# sr_controller_v0.net
KiCad netlist of a schematic drawn in EAGLE
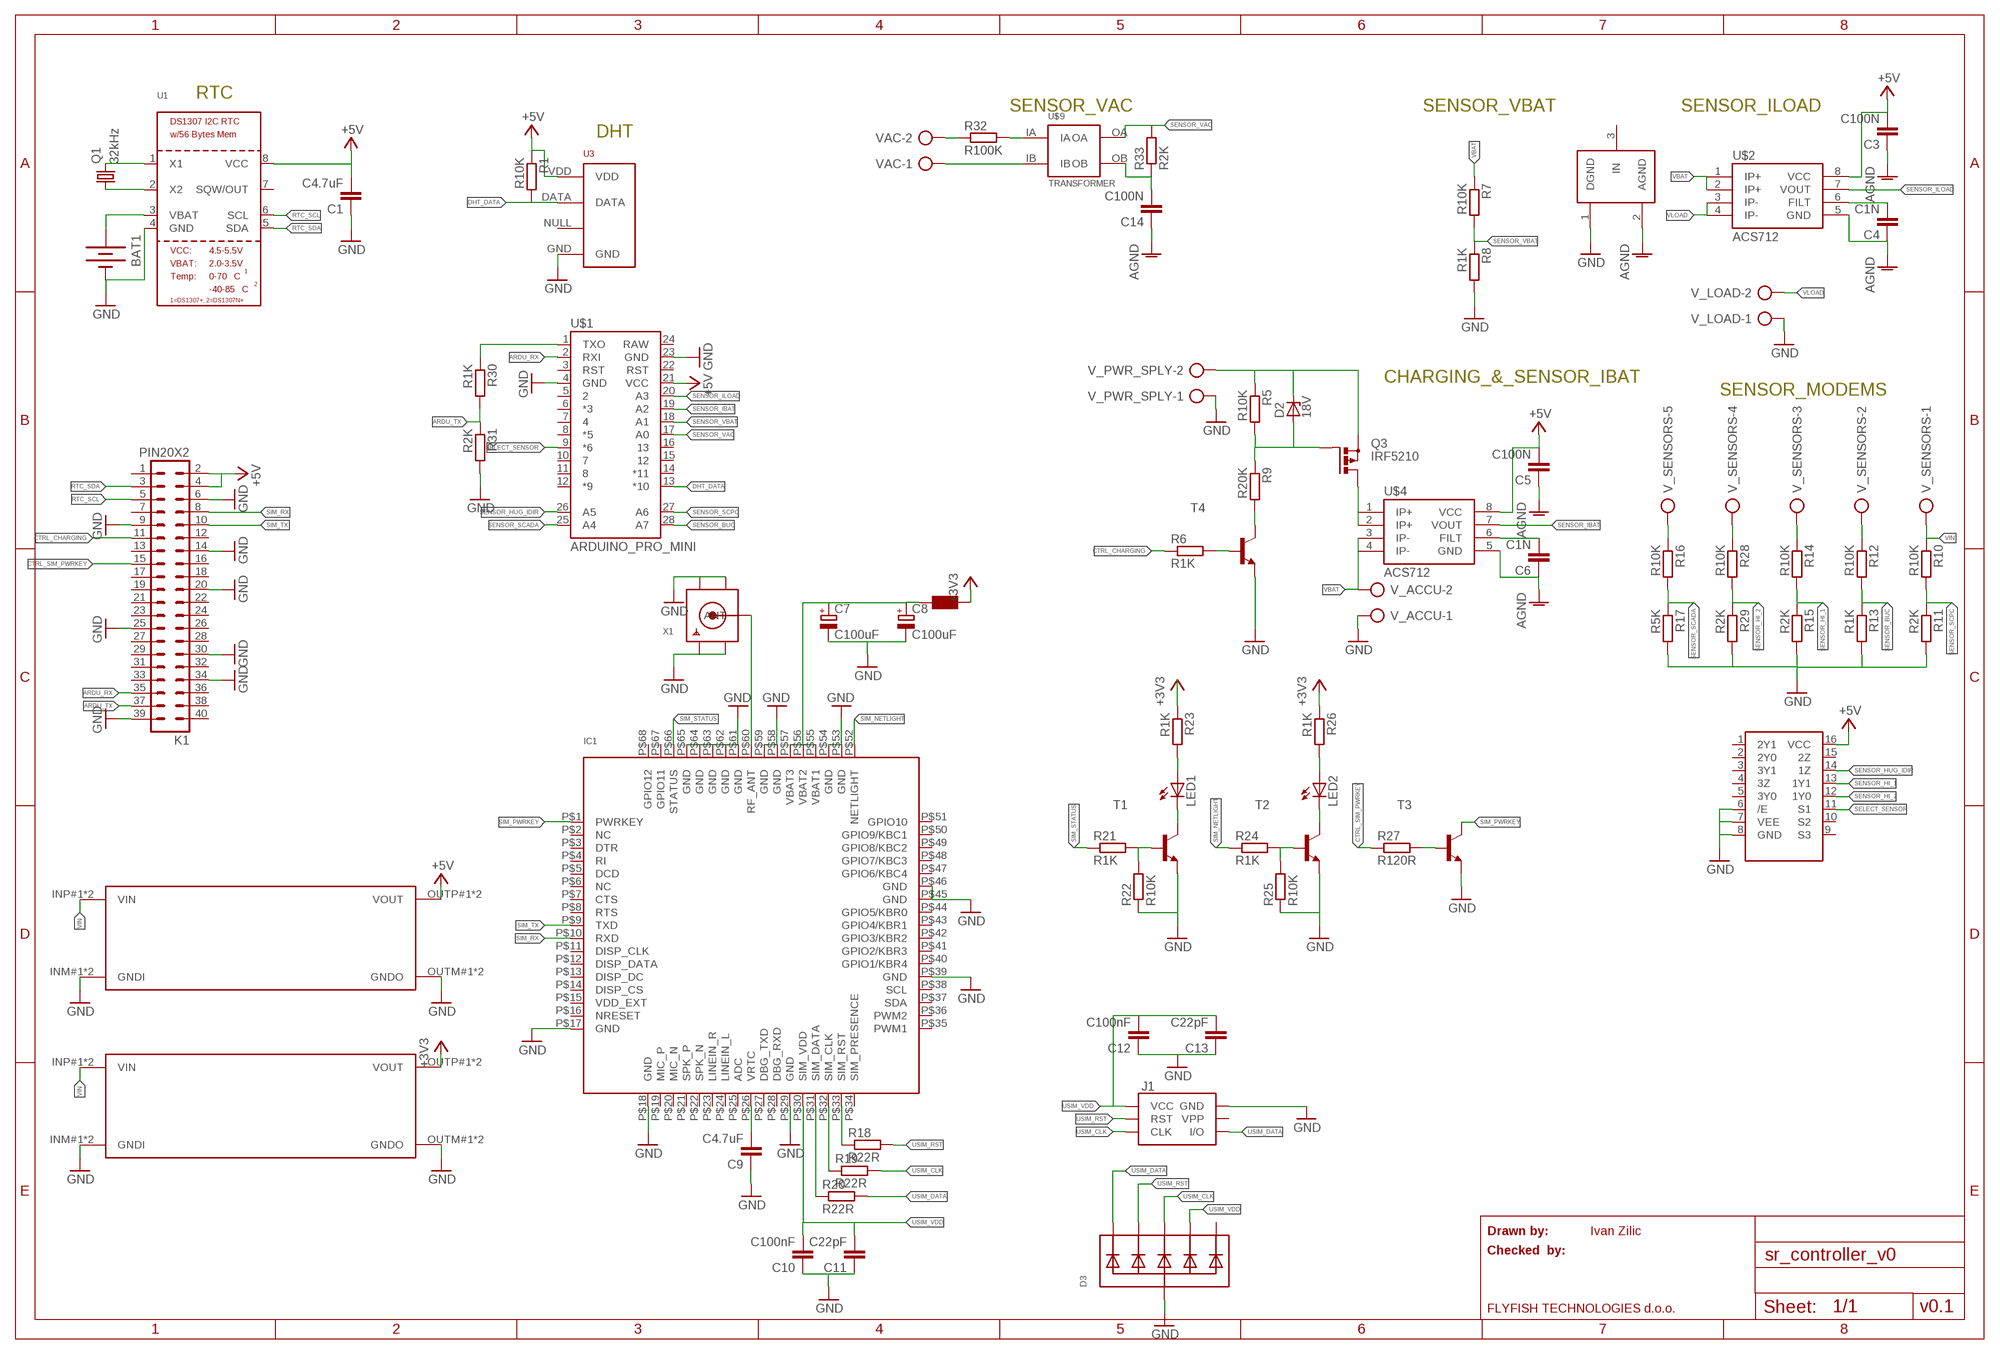
[diagram p0: schematic, sheet 1]

(export (version "E")
  (design (tool "Eeschema 10.0.6"))
  (components
    (comp (ref "BAT1")
      (value "BATTERY20PTH")
      (footprint "eagle-import:BATTCOM_20MM_PTH")
      (libsource (lib "eagle-import") (part "BATTERY20PTH"))
    )
    (comp (ref "C1")
      (value "C4.7uF")
      (footprint "eagle-import:C0805")
      (libsource (lib "eagle-import") (part "C-EUC0805"))
    )
    (comp (ref "C3")
      (value "C100N")
      (footprint "eagle-import:C0805K")
      (libsource (lib "eagle-import") (part "C-EUC0805K"))
    )
    (comp (ref "C4")
      (value "C1N")
      (footprint "eagle-import:C0805K")
      (libsource (lib "eagle-import") (part "C-EUC0805K"))
    )
    (comp (ref "C5")
      (value "C100N")
      (footprint "eagle-import:C0805K")
      (libsource (lib "eagle-import") (part "C-EUC0805K"))
    )
    (comp (ref "C6")
      (value "C1N")
      (footprint "eagle-import:C0805K")
      (libsource (lib "eagle-import") (part "C-EUC0805K"))
    )
    (comp (ref "C7")
      (value "C100uF")
      (footprint "eagle-import:153CLV-0605")
      (libsource (lib "eagle-import") (part "CPOL-EU153CLV-0605"))
    )
    (comp (ref "C8")
      (value "C100uF")
      (footprint "eagle-import:153CLV-0605")
      (libsource (lib "eagle-import") (part "CPOL-EU153CLV-0605"))
    )
    (comp (ref "C9")
      (value "C4.7uF")
      (footprint "eagle-import:C0805")
      (libsource (lib "eagle-import") (part "C-EUC0805"))
    )
    (comp (ref "C10")
      (value "C100nF")
      (footprint "eagle-import:C0805")
      (libsource (lib "eagle-import") (part "C-EUC0805"))
    )
    (comp (ref "C11")
      (value "C22pF")
      (footprint "eagle-import:C0805")
      (libsource (lib "eagle-import") (part "C-EUC0805"))
    )
    (comp (ref "C12")
      (value "C100nF")
      (footprint "eagle-import:C0805")
      (libsource (lib "eagle-import") (part "C-EUC0805"))
    )
    (comp (ref "C13")
      (value "C22pF")
      (footprint "eagle-import:C0805")
      (libsource (lib "eagle-import") (part "C-EUC0805"))
    )
    (comp (ref "C14")
      (value "C100N")
      (footprint "eagle-import:C0805K")
      (libsource (lib "eagle-import") (part "C-EUC0805K"))
    )
    (comp (ref "D2")
      (value "18V")
      (footprint "eagle-import:DO41Z10")
      (libsource (lib "eagle-import") (part "ZENER-DIODEDO41Z10"))
    )
    (comp (ref "D3")
      (value "TVSARRAY_5LANE")
      (footprint "eagle-import:SOT363")
      (libsource (lib "eagle-import") (part "TVSARRAY_5LANE"))
    )
    (comp (ref "IC1")
      (value "GSM_SIM900_LITERAL")
      (footprint "eagle-import:SIM900_SMT")
      (libsource (lib "eagle-import") (part "GSM_SIM900_LITERAL"))
    )
    (comp (ref "J1")
      (value "SIMHOLDERSIM")
      (footprint "eagle-import:SIMHOLDER")
      (libsource (lib "eagle-import") (part "SIMHOLDERSIM"))
    )
    (comp (ref "K1")
      (value "PIN20X2")
      (footprint "eagle-import:PIN_20X2")
      (libsource (lib "eagle-import") (part "PIN20X2"))
    )
    (comp (ref "LED1")
      (value "LEDCHIPLED_0805")
      (footprint "eagle-import:CHIPLED_0805")
      (libsource (lib "eagle-import") (part "LEDCHIPLED_0805"))
    )
    (comp (ref "LED2")
      (value "LEDCHIPLED_0805")
      (footprint "eagle-import:CHIPLED_0805")
      (libsource (lib "eagle-import") (part "LEDCHIPLED_0805"))
    )
    (comp (ref "Q1")
      (value "32kHz")
      (footprint "eagle-import:TC38H")
      (libsource (lib "eagle-import") (part "CRYSTALTC38H"))
    )
    (comp (ref "Q3")
      (value "IRF5210")
      (footprint "eagle-import:TO220BV")
      (libsource (lib "eagle-import") (part "PMOSFET_PTO220BV"))
    )
    (comp (ref "R1")
      (value "R10K")
      (footprint "eagle-import:R0805")
      (libsource (lib "eagle-import") (part "R-EU_R0805"))
    )
    (comp (ref "R5")
      (value "R10K")
      (footprint "eagle-import:R0805")
      (libsource (lib "eagle-import") (part "R-EU_R0805"))
    )
    (comp (ref "R6")
      (value "R1K")
      (footprint "eagle-import:R0805")
      (libsource (lib "eagle-import") (part "R-EU_R0805"))
    )
    (comp (ref "R7")
      (value "R10K")
      (footprint "eagle-import:R0805")
      (libsource (lib "eagle-import") (part "R-EU_R0805"))
    )
    (comp (ref "R8")
      (value "R1K")
      (footprint "eagle-import:R0805")
      (libsource (lib "eagle-import") (part "R-EU_R0805"))
    )
    (comp (ref "R9")
      (value "R20K")
      (footprint "eagle-import:R0805")
      (libsource (lib "eagle-import") (part "R-EU_R0805"))
    )
    (comp (ref "R10")
      (value "R10K")
      (footprint "eagle-import:R0805")
      (libsource (lib "eagle-import") (part "R-EU_R0805"))
    )
    (comp (ref "R11")
      (value "R2K")
      (footprint "eagle-import:R0805")
      (libsource (lib "eagle-import") (part "R-EU_R0805"))
    )
    (comp (ref "R12")
      (value "R10K")
      (footprint "eagle-import:R0805")
      (libsource (lib "eagle-import") (part "R-EU_R0805"))
    )
    (comp (ref "R13")
      (value "R1K")
      (footprint "eagle-import:R0805")
      (libsource (lib "eagle-import") (part "R-EU_R0805"))
    )
    (comp (ref "R14")
      (value "R10K")
      (footprint "eagle-import:R0805")
      (libsource (lib "eagle-import") (part "R-EU_R0805"))
    )
    (comp (ref "R15")
      (value "R2K")
      (footprint "eagle-import:R0805")
      (libsource (lib "eagle-import") (part "R-EU_R0805"))
    )
    (comp (ref "R16")
      (value "R10K")
      (footprint "eagle-import:R0805")
      (libsource (lib "eagle-import") (part "R-EU_R0805"))
    )
    (comp (ref "R17")
      (value "R5K")
      (footprint "eagle-import:R0805")
      (libsource (lib "eagle-import") (part "R-EU_R0805"))
    )
    (comp (ref "R18")
      (value "R22R")
      (footprint "eagle-import:R0805")
      (libsource (lib "eagle-import") (part "R-EU_R0805"))
    )
    (comp (ref "R19")
      (value "R22R")
      (footprint "eagle-import:R0805")
      (libsource (lib "eagle-import") (part "R-EU_R0805"))
    )
    (comp (ref "R20")
      (value "R22R")
      (footprint "eagle-import:R0805")
      (libsource (lib "eagle-import") (part "R-EU_R0805"))
    )
    (comp (ref "R21")
      (value "R1K")
      (footprint "eagle-import:R0805")
      (libsource (lib "eagle-import") (part "R-EU_R0805"))
    )
    (comp (ref "R22")
      (value "R10K")
      (footprint "eagle-import:R0805")
      (libsource (lib "eagle-import") (part "R-EU_R0805"))
    )
    (comp (ref "R23")
      (value "R1K")
      (footprint "eagle-import:R0805")
      (libsource (lib "eagle-import") (part "R-EU_R0805"))
    )
    (comp (ref "R24")
      (value "R1K")
      (footprint "eagle-import:R0805")
      (libsource (lib "eagle-import") (part "R-EU_R0805"))
    )
    (comp (ref "R25")
      (value "R10K")
      (footprint "eagle-import:R0805")
      (libsource (lib "eagle-import") (part "R-EU_R0805"))
    )
    (comp (ref "R26")
      (value "R1K")
      (footprint "eagle-import:R0805")
      (libsource (lib "eagle-import") (part "R-EU_R0805"))
    )
    (comp (ref "R27")
      (value "R120R")
      (footprint "eagle-import:R0805")
      (libsource (lib "eagle-import") (part "R-EU_R0805"))
    )
    (comp (ref "R28")
      (value "R10K")
      (footprint "eagle-import:R0805")
      (libsource (lib "eagle-import") (part "R-EU_R0805"))
    )
    (comp (ref "R29")
      (value "R2K")
      (footprint "eagle-import:R0805")
      (libsource (lib "eagle-import") (part "R-EU_R0805"))
    )
    (comp (ref "R30")
      (value "R1K")
      (footprint "eagle-import:R0805")
      (libsource (lib "eagle-import") (part "R-EU_R0805"))
    )
    (comp (ref "R31")
      (value "R2K")
      (footprint "eagle-import:R0805")
      (libsource (lib "eagle-import") (part "R-EU_R0805"))
    )
    (comp (ref "R32")
      (value "R100K")
      (footprint "eagle-import:0309V")
      (libsource (lib "eagle-import") (part "R-EU_0309/V"))
    )
    (comp (ref "R33")
      (value "R2K")
      (footprint "eagle-import:0309V")
      (libsource (lib "eagle-import") (part "R-EU_0309/V"))
    )
    (comp (ref "T1")
      (value "MMBT2222ALT1-NPN-SOT23-BEC")
      (footprint "eagle-import:SOT23-BEC")
      (libsource (lib "eagle-import") (part "-NPN-SOT23-BECMMBT2222ALT1"))
    )
    (comp (ref "T2")
      (value "MMBT2222ALT1-NPN-SOT23-BEC")
      (footprint "eagle-import:SOT23-BEC")
      (libsource (lib "eagle-import") (part "-NPN-SOT23-BECMMBT2222ALT1"))
    )
    (comp (ref "T3")
      (value "MMBT2222ALT1-NPN-SOT23-BEC")
      (footprint "eagle-import:SOT23-BEC")
      (libsource (lib "eagle-import") (part "-NPN-SOT23-BECMMBT2222ALT1"))
    )
    (comp (ref "T4")
      (value "MMBT2222ALT1-NPN-SOT23-BEC")
      (footprint "eagle-import:SOT23-BEC")
      (libsource (lib "eagle-import") (part "-NPN-SOT23-BECMMBT2222ALT1"))
    )
    (comp (ref "U$1")
      (value "ARDUINO_PRO_MINI")
      (footprint "eagle-import:ARDUINO_PRO_MINI")
      (libsource (lib "eagle-import") (part "ARDUINO_PRO_MINI"))
    )
    (comp (ref "U$2")
      (value "ACS712")
      (footprint "eagle-import:SO08")
      (libsource (lib "eagle-import") (part "ACS712"))
    )
    (comp (ref "U$3")
      (value "GND_CONNECT")
      (footprint "eagle-import:GND_CONNECT")
      (libsource (lib "eagle-import") (part "GND_CONNECT"))
    )
    (comp (ref "U$4")
      (value "ACS712")
      (footprint "eagle-import:SO08")
      (libsource (lib "eagle-import") (part "ACS712"))
    )
    (comp (ref "U$5")
      (value "FB0603")
      (footprint "eagle-import:L0603")
      (libsource (lib "eagle-import") (part "L0603"))
    )
    (comp (ref "U$6")
      (value "DCDCMODULE_SMALL")
      (footprint "eagle-import:DCDCMODULE-SMALL")
      (libsource (lib "eagle-import") (part "DCDCMODULE_SMALL"))
    )
    (comp (ref "U$7")
      (value "DCDCMODULE_SMALL")
      (footprint "eagle-import:DCDCMODULE-SMALL")
      (libsource (lib "eagle-import") (part "DCDCMODULE_SMALL"))
    )
    (comp (ref "U$8")
      (value "74HC4053D")
      (footprint "eagle-import:SO16")
      (libsource (lib "eagle-import") (part "74HC4053D"))
    )
    (comp (ref "U$9")
      (value "TRANSFORMER")
      (footprint "eagle-import:TV16")
      (libsource (lib "eagle-import") (part "TRANSFORMER"))
    )
    (comp (ref "U1")
      (value "RTC_DS1307")
      (footprint "eagle-import:SOIC8_150MIL")
      (libsource (lib "eagle-import") (part "RTC_DS1307"))
    )
    (comp (ref "U3")
      (value "RHT03_DHT-22_AM2302")
      (footprint "eagle-import:RHT03_DHT-22")
      (libsource (lib "eagle-import") (part "RHT03_DHT-22_AM2302"))
    )
    (comp (ref "VAC")
      (value "AK300/2")
      (footprint "eagle-import:AK300_2")
      (libsource (lib "eagle-import") (part "AK300/2"))
    )
    (comp (ref "V_ACCU")
      (value "AK300/2")
      (footprint "eagle-import:AK300_2")
      (libsource (lib "eagle-import") (part "AK300/2"))
    )
    (comp (ref "V_LOAD")
      (value "AK300/2")
      (footprint "eagle-import:AK300_2")
      (libsource (lib "eagle-import") (part "AK300/2"))
    )
    (comp (ref "V_PWR_SPLY")
      (value "AK300/2")
      (footprint "eagle-import:AK300_2")
      (libsource (lib "eagle-import") (part "AK300/2"))
    )
    (comp (ref "V_SENSORS")
      (value "AK300/5")
      (footprint "eagle-import:AK300_5")
      (libsource (lib "eagle-import") (part "AK300/5"))
    )
    (comp (ref "X1")
      (value "SMACONNECTOR")
      (footprint "eagle-import:SMA90_DIP")
      (libsource (lib "eagle-import") (part "SMACONNECTOR"))
    )
  )
  (nets
    (net (code "1") (name "+3V3") (class "Default")
      (node (ref "R23") (pin "1") (pinfunction "1_1") (pintype "passive"))
      (node (ref "R26") (pin "1") (pinfunction "1_1") (pintype "passive"))
      (node (ref "U$5") (pin "2") (pinfunction "P$2_2") (pintype "bidirectional"))
      (node (ref "U$7") (pin "OUTP#1") (pinfunction "VOUT_OUTP#1") (pintype "bidirectional"))
      (node (ref "U$7") (pin "OUTP#2") (pinfunction "VOUT_OUTP#2") (pintype "bidirectional"))
    )
    (net (code "2") (name "+5V") (class "Default")
      (node (ref "C1") (pin "2") (pinfunction "2_2") (pintype "passive"))
      (node (ref "C3") (pin "2") (pinfunction "2_2") (pintype "passive"))
      (node (ref "C5") (pin "2") (pinfunction "2_2") (pintype "passive"))
      (node (ref "K1") (pin "2") (pinfunction "2_2") (pintype "passive"))
      (node (ref "K1") (pin "4") (pinfunction "4_4") (pintype "passive"))
      (node (ref "R1") (pin "1") (pinfunction "1_1") (pintype "passive"))
      (node (ref "U$1") (pin "21") (pinfunction "VCC_21") (pintype "bidirectional"))
      (node (ref "U$2") (pin "8") (pinfunction "VCC_8") (pintype "bidirectional"))
      (node (ref "U$4") (pin "8") (pinfunction "VCC_8") (pintype "bidirectional"))
      (node (ref "U$6") (pin "OUTP#1") (pinfunction "VOUT_OUTP#1") (pintype "bidirectional"))
      (node (ref "U$6") (pin "OUTP#2") (pinfunction "VOUT_OUTP#2") (pintype "bidirectional"))
      (node (ref "U$8") (pin "16") (pinfunction "VCC_16") (pintype "bidirectional"))
      (node (ref "U1") (pin "8") (pinfunction "VCC_8") (pintype "bidirectional"))
      (node (ref "U3") (pin "VDD") (pinfunction "VDD_VDD") (pintype "power_in"))
    )
    (net (code "3") (name "/GPIO11") (class "Default")
      (node (ref "IC1") (pin "P$67") (pinfunction "GPIO11_P$67") (pintype "power_in"))
    )
    (net (code "4") (name "/GPIO12") (class "Default")
      (node (ref "IC1") (pin "P$68") (pinfunction "GPIO12_P$68") (pintype "power_in"))
    )
    (net (code "5") (name "AGND") (class "Default")
      (node (ref "C14") (pin "1") (pinfunction "1_1") (pintype "passive"))
      (node (ref "C3") (pin "1") (pinfunction "1_1") (pintype "passive"))
      (node (ref "C4") (pin "1") (pinfunction "1_1") (pintype "passive"))
      (node (ref "C5") (pin "1") (pinfunction "1_1") (pintype "passive"))
      (node (ref "C6") (pin "1") (pinfunction "1_1") (pintype "passive"))
      (node (ref "U$2") (pin "5") (pinfunction "GND_5") (pintype "bidirectional"))
      (node (ref "U$3") (pin "2") (pinfunction "AGND_2") (pintype "bidirectional"))
      (node (ref "U$4") (pin "5") (pinfunction "GND_5") (pintype "bidirectional"))
    )
    (net (code "6") (name "ARDU_RX") (class "Default")
      (node (ref "K1") (pin "35") (pinfunction "35_35") (pintype "passive"))
      (node (ref "U$1") (pin "2") (pinfunction "RXI_2") (pintype "bidirectional"))
    )
    (net (code "7") (name "ARDU_TX") (class "Default")
      (node (ref "K1") (pin "37") (pinfunction "37_37") (pintype "passive"))
      (node (ref "R30") (pin "2") (pinfunction "2_2") (pintype "passive"))
      (node (ref "R31") (pin "1") (pinfunction "1_1") (pintype "passive"))
    )
    (net (code "8") (name "CTRL_CHARGING") (class "Default")
      (node (ref "K1") (pin "11") (pinfunction "11_11") (pintype "passive"))
      (node (ref "R6") (pin "1") (pinfunction "1_1") (pintype "passive"))
    )
    (net (code "9") (name "CTRL_SIM_PWRKEY") (class "Default")
      (node (ref "K1") (pin "15") (pinfunction "15_15") (pintype "passive"))
      (node (ref "R27") (pin "1") (pinfunction "1_1") (pintype "passive"))
    )
    (net (code "10") (name "DHT_DATA") (class "Default")
      (node (ref "R1") (pin "2") (pinfunction "2_2") (pintype "passive"))
      (node (ref "U$1") (pin "13") (pinfunction "*10_13") (pintype "bidirectional"))
      (node (ref "U3") (pin "DATA") (pinfunction "DATA_DATA") (pintype "bidirectional"))
    )
    (net (code "11") (name "GND") (class "Default")
      (node (ref "BAT1") (pin "2") (pinfunction "-_2") (pintype "power_in"))
      (node (ref "C1") (pin "1") (pinfunction "1_1") (pintype "passive"))
      (node (ref "C10") (pin "1") (pinfunction "1_1") (pintype "passive"))
      (node (ref "C11") (pin "1") (pinfunction "1_1") (pintype "passive"))
      (node (ref "C12") (pin "1") (pinfunction "1_1") (pintype "passive"))
      (node (ref "C13") (pin "1") (pinfunction "1_1") (pintype "passive"))
      (node (ref "C7") (pin "-") (pinfunction "-_-") (pintype "passive"))
      (node (ref "C8") (pin "-") (pinfunction "-_-") (pintype "passive"))
      (node (ref "C9") (pin "1") (pinfunction "1_1") (pintype "passive"))
      (node (ref "D3") (pin "2") (pinfunction "A_2") (pintype "passive"))
      (node (ref "IC1") (pin "P$17") (pinfunction "GND_P$17") (pintype "power_in"))
      (node (ref "IC1") (pin "P$18") (pinfunction "GND_P$18") (pintype "power_in"))
      (node (ref "IC1") (pin "P$29") (pinfunction "GND_P$29") (pintype "power_in"))
      (node (ref "IC1") (pin "P$39") (pinfunction "GND_P$39") (pintype "power_in"))
      (node (ref "IC1") (pin "P$45") (pinfunction "GND_P$45") (pintype "power_in"))
      (node (ref "IC1") (pin "P$46") (pinfunction "GND_P$46") (pintype "power_in"))
      (node (ref "IC1") (pin "P$53") (pinfunction "GND_P$53") (pintype "power_in"))
      (node (ref "IC1") (pin "P$54") (pinfunction "GND_P$54") (pintype "power_in"))
      (node (ref "IC1") (pin "P$58") (pinfunction "GND_P$58") (pintype "power_in"))
      (node (ref "IC1") (pin "P$59") (pinfunction "GND_P$59") (pintype "power_in"))
      (node (ref "IC1") (pin "P$61") (pinfunction "GND_P$61") (pintype "power_in"))
      (node (ref "IC1") (pin "P$62") (pinfunction "GND_P$62") (pintype "power_in"))
      (node (ref "IC1") (pin "P$63") (pinfunction "GND_P$63") (pintype "power_in"))
      (node (ref "IC1") (pin "P$64") (pinfunction "GND_P$64") (pintype "power_in"))
      (node (ref "IC1") (pin "P$65") (pinfunction "GND_P$65") (pintype "power_in"))
      (node (ref "J1") (pin "C5") (pinfunction "GND_C5") (pintype "power_in"))
      (node (ref "K1") (pin "14") (pinfunction "14_14") (pintype "passive"))
      (node (ref "K1") (pin "20") (pinfunction "20_20") (pintype "passive"))
      (node (ref "K1") (pin "25") (pinfunction "25_25") (pintype "passive"))
      (node (ref "K1") (pin "30") (pinfunction "30_30") (pintype "passive"))
      (node (ref "K1") (pin "34") (pinfunction "34_34") (pintype "passive"))
      (node (ref "K1") (pin "39") (pinfunction "39_39") (pintype "passive"))
      (node (ref "K1") (pin "6") (pinfunction "6_6") (pintype "passive"))
      (node (ref "K1") (pin "9") (pinfunction "9_9") (pintype "passive"))
      (node (ref "R11") (pin "2") (pinfunction "2_2") (pintype "passive"))
      (node (ref "R13") (pin "2") (pinfunction "2_2") (pintype "passive"))
      (node (ref "R15") (pin "2") (pinfunction "2_2") (pintype "passive"))
      (node (ref "R17") (pin "2") (pinfunction "2_2") (pintype "passive"))
      (node (ref "R22") (pin "1") (pinfunction "1_1") (pintype "passive"))
      (node (ref "R25") (pin "1") (pinfunction "1_1") (pintype "passive"))
      (node (ref "R29") (pin "2") (pinfunction "2_2") (pintype "passive"))
      (node (ref "R31") (pin "2") (pinfunction "2_2") (pintype "passive"))
      (node (ref "R8") (pin "2") (pinfunction "2_2") (pintype "passive"))
      (node (ref "T1") (pin "E") (pinfunction "E_E") (pintype "passive"))
      (node (ref "T2") (pin "E") (pinfunction "E_E") (pintype "passive"))
      (node (ref "T3") (pin "E") (pinfunction "E_E") (pintype "passive"))
      (node (ref "T4") (pin "E") (pinfunction "E_E") (pintype "passive"))
      (node (ref "U$1") (pin "23") (pinfunction "GND_23") (pintype "bidirectional"))
      (node (ref "U$1") (pin "4") (pinfunction "GND_4") (pintype "bidirectional"))
      (node (ref "U$3") (pin "1") (pinfunction "DGND_1") (pintype "bidirectional"))
      (node (ref "U$6") (pin "INM#1") (pinfunction "GNDI_INM#1") (pintype "bidirectional"))
      (node (ref "U$6") (pin "INM#2") (pinfunction "GNDI_INM#2") (pintype "bidirectional"))
      (node (ref "U$6") (pin "OUTM#1") (pinfunction "GNDO_OUTM#1") (pintype "bidirectional"))
      (node (ref "U$6") (pin "OUTM#2") (pinfunction "GNDO_OUTM#2") (pintype "bidirectional"))
      (node (ref "U$7") (pin "INM#1") (pinfunction "GNDI_INM#1") (pintype "bidirectional"))
      (node (ref "U$7") (pin "INM#2") (pinfunction "GNDI_INM#2") (pintype "bidirectional"))
      (node (ref "U$7") (pin "OUTM#1") (pinfunction "GNDO_OUTM#1") (pintype "bidirectional"))
      (node (ref "U$7") (pin "OUTM#2") (pinfunction "GNDO_OUTM#2") (pintype "bidirectional"))
      (node (ref "U$8") (pin "6") (pinfunction "/E_6") (pintype "bidirectional"))
      (node (ref "U$8") (pin "7") (pinfunction "VEE_7") (pintype "bidirectional"))
      (node (ref "U$8") (pin "8") (pinfunction "GND_8") (pintype "bidirectional"))
      (node (ref "U1") (pin "4") (pinfunction "GND_4") (pintype "bidirectional"))
      (node (ref "U3") (pin "GND") (pinfunction "GND_GND") (pintype "power_in"))
      (node (ref "V_ACCU") (pin "1") (pinfunction "KL_1") (pintype "passive"))
      (node (ref "V_LOAD") (pin "1") (pinfunction "KL_1") (pintype "passive"))
      (node (ref "V_PWR_SPLY") (pin "1") (pinfunction "KL_1") (pintype "passive"))
      (node (ref "X1") (pin "GND1") (pinfunction "GND1_GND1") (pintype "power_in"))
      (node (ref "X1") (pin "GND2") (pinfunction "GND2_GND2") (pintype "power_in"))
      (node (ref "X1") (pin "GND3") (pinfunction "GND3_GND3") (pintype "power_in"))
      (node (ref "X1") (pin "GND4") (pinfunction "GND4_GND4") (pintype "power_in"))
    )
    (net (code "12") (name "Net-(BAT1-+)") (class "Default")
      (node (ref "BAT1") (pin "1") (pinfunction "+_1") (pintype "power_in"))
      (node (ref "U1") (pin "3") (pinfunction "VBAT_3") (pintype "bidirectional"))
    )
    (net (code "13") (name "Net-(C14-Pad2)") (class "Default")
      (node (ref "C14") (pin "2") (pinfunction "2_2") (pintype "passive"))
      (node (ref "R33") (pin "1") (pinfunction "1_1") (pintype "passive"))
      (node (ref "U$9") (pin "OB") (pinfunction "OB_OB") (pintype "bidirectional"))
    )
    (net (code "14") (name "Net-(D2-PadA)") (class "Default")
      (node (ref "D2") (pin "A") (pinfunction "A_A") (pintype "passive"))
      (node (ref "Q3") (pin "G") (pinfunction "G_G") (pintype "passive"))
      (node (ref "R5") (pin "2") (pinfunction "2_2") (pintype "passive"))
      (node (ref "R9") (pin "1") (pinfunction "1_1") (pintype "passive"))
    )
    (net (code "15") (name "Net-(IC1-RF_ANT)") (class "Default")
      (node (ref "IC1") (pin "P$60") (pinfunction "RF_ANT_P$60") (pintype "bidirectional"))
      (node (ref "X1") (pin "ANTENNA") (pinfunction "ANT_ANTENNA") (pintype "bidirectional"))
    )
    (net (code "16") (name "Net-(IC1-SIM_CLK)") (class "Default")
      (node (ref "IC1") (pin "P$32") (pinfunction "SIM_CLK_P$32") (pintype "bidirectional"))
      (node (ref "R19") (pin "1") (pinfunction "1_1") (pintype "passive"))
    )
    (net (code "17") (name "Net-(IC1-SIM_DATA)") (class "Default")
      (node (ref "IC1") (pin "P$31") (pinfunction "SIM_DATA_P$31") (pintype "bidirectional"))
      (node (ref "R20") (pin "1") (pinfunction "1_1") (pintype "passive"))
    )
    (net (code "18") (name "Net-(IC1-SIM_RST)") (class "Default")
      (node (ref "IC1") (pin "P$33") (pinfunction "SIM_RST_P$33") (pintype "bidirectional"))
      (node (ref "R18") (pin "1") (pinfunction "1_1") (pintype "passive"))
    )
    (net (code "19") (name "Net-(IC1-VBAT1)") (class "Default")
      (node (ref "C7") (pin "+") (pinfunction "+_+") (pintype "passive"))
      (node (ref "C8") (pin "+") (pinfunction "+_+") (pintype "passive"))
      (node (ref "IC1") (pin "P$55") (pinfunction "VBAT1_P$55") (pintype "power_in"))
      (node (ref "IC1") (pin "P$56") (pinfunction "VBAT2_P$56") (pintype "power_in"))
      (node (ref "IC1") (pin "P$57") (pinfunction "VBAT3_P$57") (pintype "power_in"))
      (node (ref "U$5") (pin "1") (pinfunction "P$1_1") (pintype "bidirectional"))
    )
    (net (code "20") (name "Net-(IC1-VRTC)") (class "Default")
      (node (ref "C9") (pin "2") (pinfunction "2_2") (pintype "passive"))
      (node (ref "IC1") (pin "P$26") (pinfunction "VRTC_P$26") (pintype "power_in"))
    )
    (net (code "21") (name "Net-(LED1-PadA)") (class "Default")
      (node (ref "LED1") (pin "A") (pinfunction "A_A") (pintype "passive"))
      (node (ref "R23") (pin "2") (pinfunction "2_2") (pintype "passive"))
    )
    (net (code "22") (name "Net-(LED1-PadC)") (class "Default")
      (node (ref "LED1") (pin "C") (pinfunction "C_C") (pintype "passive"))
      (node (ref "T1") (pin "C") (pinfunction "C_C") (pintype "passive"))
    )
    (net (code "23") (name "Net-(LED2-PadA)") (class "Default")
      (node (ref "LED2") (pin "A") (pinfunction "A_A") (pintype "passive"))
      (node (ref "R26") (pin "2") (pinfunction "2_2") (pintype "passive"))
    )
    (net (code "24") (name "Net-(LED2-PadC)") (class "Default")
      (node (ref "LED2") (pin "C") (pinfunction "C_C") (pintype "passive"))
      (node (ref "T2") (pin "C") (pinfunction "C_C") (pintype "passive"))
    )
    (net (code "25") (name "Net-(Q3-PadD)") (class "Default")
      (node (ref "Q3") (pin "D") (pinfunction "D_D") (pintype "passive"))
      (node (ref "U$4") (pin "1") (pinfunction "IP+_1") (pintype "bidirectional"))
      (node (ref "U$4") (pin "2") (pinfunction "IP+_2") (pintype "bidirectional"))
    )
    (net (code "26") (name "Net-(R6-Pad2)") (class "Default")
      (node (ref "R6") (pin "2") (pinfunction "2_2") (pintype "passive"))
      (node (ref "T4") (pin "B") (pinfunction "B_B") (pintype "passive"))
    )
    (net (code "27") (name "Net-(R9-Pad2)") (class "Default")
      (node (ref "R9") (pin "2") (pinfunction "2_2") (pintype "passive"))
      (node (ref "T4") (pin "C") (pinfunction "C_C") (pintype "passive"))
    )
    (net (code "28") (name "Net-(R21-Pad2)") (class "Default")
      (node (ref "R21") (pin "2") (pinfunction "2_2") (pintype "passive"))
      (node (ref "R22") (pin "2") (pinfunction "2_2") (pintype "passive"))
      (node (ref "T1") (pin "B") (pinfunction "B_B") (pintype "passive"))
    )
    (net (code "29") (name "Net-(R24-Pad2)") (class "Default")
      (node (ref "R24") (pin "2") (pinfunction "2_2") (pintype "passive"))
      (node (ref "R25") (pin "2") (pinfunction "2_2") (pintype "passive"))
      (node (ref "T2") (pin "B") (pinfunction "B_B") (pintype "passive"))
    )
    (net (code "30") (name "Net-(R27-Pad2)") (class "Default")
      (node (ref "R27") (pin "2") (pinfunction "2_2") (pintype "passive"))
      (node (ref "T3") (pin "B") (pinfunction "B_B") (pintype "passive"))
    )
    (net (code "31") (name "Net-(R32-Pad2)") (class "Default")
      (node (ref "R32") (pin "2") (pinfunction "2_2") (pintype "passive"))
      (node (ref "U$9") (pin "IA") (pinfunction "IA_IA") (pintype "bidirectional"))
    )
    (net (code "32") (name "Net-(U$1-TXO)") (class "Default")
      (node (ref "R30") (pin "1") (pinfunction "1_1") (pintype "passive"))
      (node (ref "U$1") (pin "1") (pinfunction "TXO_1") (pintype "bidirectional"))
    )
    (net (code "33") (name "Net-(U$2-FILT)") (class "Default")
      (node (ref "C4") (pin "2") (pinfunction "2_2") (pintype "passive"))
      (node (ref "U$2") (pin "6") (pinfunction "FILT_6") (pintype "bidirectional"))
    )
    (net (code "34") (name "Net-(U$4-FILT)") (class "Default")
      (node (ref "C6") (pin "2") (pinfunction "2_2") (pintype "passive"))
      (node (ref "U$4") (pin "6") (pinfunction "FILT_6") (pintype "bidirectional"))
    )
    (net (code "35") (name "Net-(U1-X1)") (class "Default")
      (node (ref "Q1") (pin "2") (pinfunction "2_2") (pintype "passive"))
      (node (ref "U1") (pin "1") (pinfunction "X1_1") (pintype "bidirectional"))
    )
    (net (code "36") (name "Net-(U1-X2)") (class "Default")
      (node (ref "Q1") (pin "1") (pinfunction "1_1") (pintype "passive"))
      (node (ref "U1") (pin "2") (pinfunction "X2_2") (pintype "bidirectional"))
    )
    (net (code "37") (name "Net-(VACA-KL)") (class "Default")
      (node (ref "U$9") (pin "IB") (pinfunction "IB_IB") (pintype "bidirectional"))
      (node (ref "VAC") (pin "1") (pinfunction "KL_1") (pintype "passive"))
    )
    (net (code "38") (name "Net-(VACB-KL)") (class "Default")
      (node (ref "R32") (pin "1") (pinfunction "1_1") (pintype "passive"))
      (node (ref "VAC") (pin "2") (pinfunction "KL_2") (pintype "passive"))
    )
    (net (code "39") (name "Net-(V_PWR_SPLYB-KL)") (class "Default")
      (node (ref "D2") (pin "C") (pinfunction "C_C") (pintype "passive"))
      (node (ref "Q3") (pin "S") (pinfunction "S_S") (pintype "passive"))
      (node (ref "R5") (pin "1") (pinfunction "1_1") (pintype "passive"))
      (node (ref "V_PWR_SPLY") (pin "2") (pinfunction "KL_2") (pintype "passive"))
    )
    (net (code "40") (name "Net-(V_SENSORSB-KL)") (class "Default")
      (node (ref "R12") (pin "1") (pinfunction "1_1") (pintype "passive"))
      (node (ref "V_SENSORS") (pin "2") (pinfunction "KL_2") (pintype "passive"))
    )
    (net (code "41") (name "Net-(V_SENSORSC-KL)") (class "Default")
      (node (ref "R14") (pin "1") (pinfunction "1_1") (pintype "passive"))
      (node (ref "V_SENSORS") (pin "3") (pinfunction "KL_3") (pintype "passive"))
    )
    (net (code "42") (name "Net-(V_SENSORSD-KL)") (class "Default")
      (node (ref "R28") (pin "1") (pinfunction "1_1") (pintype "passive"))
      (node (ref "V_SENSORS") (pin "4") (pinfunction "KL_4") (pintype "passive"))
    )
    (net (code "43") (name "Net-(V_SENSORSE-KL)") (class "Default")
      (node (ref "R16") (pin "1") (pinfunction "1_1") (pintype "passive"))
      (node (ref "V_SENSORS") (pin "5") (pinfunction "KL_5") (pintype "passive"))
    )
    (net (code "44") (name "RTC_SCL") (class "Default")
      (node (ref "K1") (pin "5") (pinfunction "5_5") (pintype "passive"))
      (node (ref "U1") (pin "6") (pinfunction "SCL_6") (pintype "bidirectional"))
    )
    (net (code "45") (name "RTC_SDA") (class "Default")
      (node (ref "K1") (pin "3") (pinfunction "3_3") (pintype "passive"))
      (node (ref "U1") (pin "5") (pinfunction "SDA_5") (pintype "bidirectional"))
    )
    (net (code "46") (name "SELECT_SENSOR") (class "Default")
      (node (ref "U$1") (pin "9") (pinfunction "*6_9") (pintype "bidirectional"))
      (node (ref "U$8") (pin "11") (pinfunction "S1_11") (pintype "bidirectional"))
    )
    (net (code "47") (name "SENSOR_BUC") (class "Default")
      (node (ref "R12") (pin "2") (pinfunction "2_2") (pintype "passive"))
      (node (ref "R13") (pin "1") (pinfunction "1_1") (pintype "passive"))
      (node (ref "U$1") (pin "28") (pinfunction "A7_28") (pintype "bidirectional"))
    )
    (net (code "48") (name "SENSOR_HI_1") (class "Default")
      (node (ref "R14") (pin "2") (pinfunction "2_2") (pintype "passive"))
      (node (ref "R15") (pin "1") (pinfunction "1_1") (pintype "passive"))
      (node (ref "U$8") (pin "13") (pinfunction "1Y1_13") (pintype "bidirectional"))
    )
    (net (code "49") (name "SENSOR_HI_2") (class "Default")
      (node (ref "R28") (pin "2") (pinfunction "2_2") (pintype "passive"))
      (node (ref "R29") (pin "1") (pinfunction "1_1") (pintype "passive"))
      (node (ref "U$8") (pin "12") (pinfunction "1Y0_12") (pintype "bidirectional"))
    )
    (net (code "50") (name "SENSOR_HUG_IDIR") (class "Default")
      (node (ref "U$1") (pin "26") (pinfunction "A5_26") (pintype "bidirectional"))
      (node (ref "U$8") (pin "14") (pinfunction "1Z_14") (pintype "bidirectional"))
    )
    (net (code "51") (name "SENSOR_IBAT") (class "Default")
      (node (ref "U$1") (pin "19") (pinfunction "A2_19") (pintype "bidirectional"))
      (node (ref "U$4") (pin "7") (pinfunction "VOUT_7") (pintype "bidirectional"))
    )
    (net (code "52") (name "SENSOR_ILOAD") (class "Default")
      (node (ref "U$1") (pin "20") (pinfunction "A3_20") (pintype "bidirectional"))
      (node (ref "U$2") (pin "7") (pinfunction "VOUT_7") (pintype "bidirectional"))
    )
    (net (code "53") (name "SENSOR_SCADA") (class "Default")
      (node (ref "R16") (pin "2") (pinfunction "2_2") (pintype "passive"))
      (node (ref "R17") (pin "1") (pinfunction "1_1") (pintype "passive"))
      (node (ref "U$1") (pin "25") (pinfunction "A4_25") (pintype "bidirectional"))
    )
    (net (code "54") (name "SENSOR_SCPC") (class "Default")
      (node (ref "R10") (pin "2") (pinfunction "2_2") (pintype "passive"))
      (node (ref "R11") (pin "1") (pinfunction "1_1") (pintype "passive"))
      (node (ref "U$1") (pin "27") (pinfunction "A6_27") (pintype "bidirectional"))
    )
    (net (code "55") (name "SENSOR_VAC") (class "Default")
      (node (ref "R33") (pin "2") (pinfunction "2_2") (pintype "passive"))
      (node (ref "U$1") (pin "17") (pinfunction "A0_17") (pintype "bidirectional"))
      (node (ref "U$9") (pin "OA") (pinfunction "OA_OA") (pintype "bidirectional"))
    )
    (net (code "56") (name "SENSOR_VBAT") (class "Default")
      (node (ref "R7") (pin "2") (pinfunction "2_2") (pintype "passive"))
      (node (ref "R8") (pin "1") (pinfunction "1_1") (pintype "passive"))
      (node (ref "U$1") (pin "18") (pinfunction "A1_18") (pintype "bidirectional"))
    )
    (net (code "57") (name "SIM_NETLIGHT") (class "Default")
      (node (ref "IC1") (pin "P$52") (pinfunction "NETLIGHT_P$52") (pintype "bidirectional"))
      (node (ref "R24") (pin "1") (pinfunction "1_1") (pintype "passive"))
    )
    (net (code "58") (name "SIM_PWRKEY") (class "Default")
      (node (ref "IC1") (pin "P$1") (pinfunction "PWRKEY_P$1") (pintype "power_in"))
      (node (ref "T3") (pin "C") (pinfunction "C_C") (pintype "passive"))
    )
    (net (code "59") (name "SIM_RX") (class "Default")
      (node (ref "IC1") (pin "P$10") (pinfunction "RXD_P$10") (pintype "input"))
      (node (ref "K1") (pin "8") (pinfunction "8_8") (pintype "passive"))
    )
    (net (code "60") (name "SIM_STATUS") (class "Default")
      (node (ref "IC1") (pin "P$66") (pinfunction "STATUS_P$66") (pintype "bidirectional"))
      (node (ref "R21") (pin "1") (pinfunction "1_1") (pintype "passive"))
    )
    (net (code "61") (name "SIM_TX") (class "Default")
      (node (ref "IC1") (pin "P$9") (pinfunction "TXD_P$9") (pintype "output"))
      (node (ref "K1") (pin "10") (pinfunction "10_10") (pintype "passive"))
    )
    (net (code "62") (name "USIM_CLK") (class "Default")
      (node (ref "D3") (pin "4") (pinfunction "C3_4") (pintype "passive"))
      (node (ref "J1") (pin "C3") (pinfunction "CLK_C3") (pintype "input"))
      (node (ref "R19") (pin "2") (pinfunction "2_2") (pintype "passive"))
    )
    (net (code "63") (name "USIM_DATA") (class "Default")
      (node (ref "D3") (pin "1") (pinfunction "C1_1") (pintype "passive"))
      (node (ref "J1") (pin "C7") (pinfunction "I/O_C7") (pintype "bidirectional"))
      (node (ref "R20") (pin "2") (pinfunction "2_2") (pintype "passive"))
    )
    (net (code "64") (name "USIM_RST") (class "Default")
      (node (ref "D3") (pin "3") (pinfunction "C2_3") (pintype "passive"))
      (node (ref "J1") (pin "C2") (pinfunction "RST_C2") (pintype "input"))
      (node (ref "R18") (pin "2") (pinfunction "2_2") (pintype "passive"))
    )
    (net (code "65") (name "USIM_VDD") (class "Default")
      (node (ref "C10") (pin "2") (pinfunction "2_2") (pintype "passive"))
      (node (ref "C11") (pin "2") (pinfunction "2_2") (pintype "passive"))
      (node (ref "C12") (pin "2") (pinfunction "2_2") (pintype "passive"))
      (node (ref "C13") (pin "2") (pinfunction "2_2") (pintype "passive"))
      (node (ref "D3") (pin "5") (pinfunction "C4_5") (pintype "passive"))
      (node (ref "IC1") (pin "P$30") (pinfunction "SIM_VDD_P$30") (pintype "power_in"))
      (node (ref "J1") (pin "C1") (pinfunction "VCC_C1") (pintype "power_in"))
    )
    (net (code "66") (name "VBAT") (class "Default")
      (node (ref "R7") (pin "1") (pinfunction "1_1") (pintype "passive"))
      (node (ref "U$2") (pin "1") (pinfunction "IP+_1") (pintype "bidirectional"))
      (node (ref "U$2") (pin "2") (pinfunction "IP+_2") (pintype "bidirectional"))
      (node (ref "U$4") (pin "3") (pinfunction "IP-_3") (pintype "bidirectional"))
      (node (ref "U$4") (pin "4") (pinfunction "IP-_4") (pintype "bidirectional"))
      (node (ref "V_ACCU") (pin "2") (pinfunction "KL_2") (pintype "passive"))
    )
    (net (code "67") (name "VIN") (class "Default")
      (node (ref "R10") (pin "1") (pinfunction "1_1") (pintype "passive"))
      (node (ref "U$6") (pin "INP#1") (pinfunction "VIN_INP#1") (pintype "bidirectional"))
      (node (ref "U$6") (pin "INP#2") (pinfunction "VIN_INP#2") (pintype "bidirectional"))
      (node (ref "U$7") (pin "INP#1") (pinfunction "VIN_INP#1") (pintype "bidirectional"))
      (node (ref "U$7") (pin "INP#2") (pinfunction "VIN_INP#2") (pintype "bidirectional"))
      (node (ref "V_SENSORS") (pin "1") (pinfunction "KL_1") (pintype "passive"))
    )
    (net (code "68") (name "VLOAD") (class "Default")
      (node (ref "U$2") (pin "3") (pinfunction "IP-_3") (pintype "bidirectional"))
      (node (ref "U$2") (pin "4") (pinfunction "IP-_4") (pintype "bidirectional"))
      (node (ref "V_LOAD") (pin "2") (pinfunction "KL_2") (pintype "passive"))
    )
    (net (code "69") (name "unconnected-(D3-C5-Pad6)") (class "Default")
      (node (ref "D3") (pin "6") (pinfunction "C5_6") (pintype "passive"))
    )
    (net (code "70") (name "unconnected-(IC1-ADC-PadP$25)") (class "Default")
      (node (ref "IC1") (pin "P$25") (pinfunction "ADC_P$25") (pintype "bidirectional"))
    )
    (net (code "71") (name "unconnected-(IC1-CTS-PadP$7)") (class "Default")
      (node (ref "IC1") (pin "P$7") (pinfunction "CTS_P$7") (pintype "output"))
    )
    (net (code "72") (name "unconnected-(IC1-DBG_RXD-PadP$28)") (class "Default")
      (node (ref "IC1") (pin "P$28") (pinfunction "DBG_RXD_P$28") (pintype "input"))
    )
    (net (code "73") (name "unconnected-(IC1-DBG_TXD-PadP$27)") (class "Default")
      (node (ref "IC1") (pin "P$27") (pinfunction "DBG_TXD_P$27") (pintype "output"))
    )
    (net (code "74") (name "unconnected-(IC1-DCD-PadP$5)") (class "Default")
      (node (ref "IC1") (pin "P$5") (pinfunction "DCD_P$5") (pintype "output"))
    )
    (net (code "75") (name "unconnected-(IC1-DISP_CLK-PadP$11)") (class "Default")
      (node (ref "IC1") (pin "P$11") (pinfunction "DISP_CLK_P$11") (pintype "bidirectional"))
    )
    (net (code "76") (name "unconnected-(IC1-DISP_CS-PadP$14)") (class "Default")
      (node (ref "IC1") (pin "P$14") (pinfunction "DISP_CS_P$14") (pintype "bidirectional"))
    )
    (net (code "77") (name "unconnected-(IC1-DISP_DATA-PadP$12)") (class "Default")
      (node (ref "IC1") (pin "P$12") (pinfunction "DISP_DATA_P$12") (pintype "bidirectional"))
    )
    (net (code "78") (name "unconnected-(IC1-DISP_DC-PadP$13)") (class "Default")
      (node (ref "IC1") (pin "P$13") (pinfunction "DISP_DC_P$13") (pintype "bidirectional"))
    )
    (net (code "79") (name "unconnected-(IC1-DTR-PadP$3)") (class "Default")
      (node (ref "IC1") (pin "P$3") (pinfunction "DTR_P$3") (pintype "input"))
    )
    (net (code "80") (name "unconnected-(IC1-GPIO1{slash}KBR4-PadP$40)") (class "Default")
      (node (ref "IC1") (pin "P$40") (pinfunction "GPIO1/KBR4_P$40") (pintype "bidirectional"))
    )
    (net (code "81") (name "unconnected-(IC1-GPIO2{slash}KBR3-PadP$41)") (class "Default")
      (node (ref "IC1") (pin "P$41") (pinfunction "GPIO2/KBR3_P$41") (pintype "bidirectional"))
    )
    (net (code "82") (name "unconnected-(IC1-GPIO3{slash}KBR2-PadP$42)") (class "Default")
      (node (ref "IC1") (pin "P$42") (pinfunction "GPIO3/KBR2_P$42") (pintype "bidirectional"))
    )
    (net (code "83") (name "unconnected-(IC1-GPIO4{slash}KBR1-PadP$43)") (class "Default")
      (node (ref "IC1") (pin "P$43") (pinfunction "GPIO4/KBR1_P$43") (pintype "bidirectional"))
    )
    (net (code "84") (name "unconnected-(IC1-GPIO5{slash}KBR0-PadP$44)") (class "Default")
      (node (ref "IC1") (pin "P$44") (pinfunction "GPIO5/KBR0_P$44") (pintype "bidirectional"))
    )
    (net (code "85") (name "unconnected-(IC1-GPIO6{slash}KBC4-PadP$47)") (class "Default")
      (node (ref "IC1") (pin "P$47") (pinfunction "GPIO6/KBC4_P$47") (pintype "bidirectional"))
    )
    (net (code "86") (name "unconnected-(IC1-GPIO7{slash}KBC3-PadP$48)") (class "Default")
      (node (ref "IC1") (pin "P$48") (pinfunction "GPIO7/KBC3_P$48") (pintype "bidirectional"))
    )
    (net (code "87") (name "unconnected-(IC1-GPIO8{slash}KBC2-PadP$49)") (class "Default")
      (node (ref "IC1") (pin "P$49") (pinfunction "GPIO8/KBC2_P$49") (pintype "bidirectional"))
    )
    (net (code "88") (name "unconnected-(IC1-GPIO9{slash}KBC1-PadP$50)") (class "Default")
      (node (ref "IC1") (pin "P$50") (pinfunction "GPIO9/KBC1_P$50") (pintype "bidirectional"))
    )
    (net (code "89") (name "unconnected-(IC1-GPIO10-PadP$51)") (class "Default")
      (node (ref "IC1") (pin "P$51") (pinfunction "GPIO10_P$51") (pintype "bidirectional"))
    )
    (net (code "90") (name "unconnected-(IC1-LINEIN_L-PadP$24)") (class "Default")
      (node (ref "IC1") (pin "P$24") (pinfunction "LINEIN_L_P$24") (pintype "bidirectional"))
    )
    (net (code "91") (name "unconnected-(IC1-LINEIN_R-PadP$23)") (class "Default")
      (node (ref "IC1") (pin "P$23") (pinfunction "LINEIN_R_P$23") (pintype "bidirectional"))
    )
    (net (code "92") (name "unconnected-(IC1-MIC_N-PadP$20)") (class "Default")
      (node (ref "IC1") (pin "P$20") (pinfunction "MIC_N_P$20") (pintype "bidirectional"))
    )
    (net (code "93") (name "unconnected-(IC1-MIC_P-PadP$19)") (class "Default")
      (node (ref "IC1") (pin "P$19") (pinfunction "MIC_P_P$19") (pintype "bidirectional"))
    )
    (net (code "94") (name "unconnected-(IC1-NC-PadP$2)") (class "Default")
      (node (ref "IC1") (pin "P$2") (pinfunction "NC_P$2") (pintype "no_connect"))
    )
    (net (code "95") (name "unconnected-(IC1-NC-PadP$6)") (class "Default")
      (node (ref "IC1") (pin "P$6") (pinfunction "NC_P$6") (pintype "no_connect"))
    )
    (net (code "96") (name "unconnected-(IC1-NRESET-PadP$16)") (class "Default")
      (node (ref "IC1") (pin "P$16") (pinfunction "NRESET_P$16") (pintype "bidirectional"))
    )
    (net (code "97") (name "unconnected-(IC1-PWM1-PadP$35)") (class "Default")
      (node (ref "IC1") (pin "P$35") (pinfunction "PWM1_P$35") (pintype "bidirectional"))
    )
    (net (code "98") (name "unconnected-(IC1-PWM2-PadP$36)") (class "Default")
      (node (ref "IC1") (pin "P$36") (pinfunction "PWM2_P$36") (pintype "bidirectional"))
    )
    (net (code "99") (name "unconnected-(IC1-RI-PadP$4)") (class "Default")
      (node (ref "IC1") (pin "P$4") (pinfunction "RI_P$4") (pintype "output"))
    )
    (net (code "100") (name "unconnected-(IC1-RTS-PadP$8)") (class "Default")
      (node (ref "IC1") (pin "P$8") (pinfunction "RTS_P$8") (pintype "input"))
    )
    (net (code "101") (name "unconnected-(IC1-SCL-PadP$38)") (class "Default")
      (node (ref "IC1") (pin "P$38") (pinfunction "SCL_P$38") (pintype "bidirectional"))
    )
    (net (code "102") (name "unconnected-(IC1-SDA-PadP$37)") (class "Default")
      (node (ref "IC1") (pin "P$37") (pinfunction "SDA_P$37") (pintype "bidirectional"))
    )
    (net (code "103") (name "unconnected-(IC1-SIM_PRESENCE-PadP$34)") (class "Default")
      (node (ref "IC1") (pin "P$34") (pinfunction "SIM_PRESENCE_P$34") (pintype "bidirectional"))
    )
    (net (code "104") (name "unconnected-(IC1-SPK_N-PadP$22)") (class "Default")
      (node (ref "IC1") (pin "P$22") (pinfunction "SPK_N_P$22") (pintype "bidirectional"))
    )
    (net (code "105") (name "unconnected-(IC1-SPK_P-PadP$21)") (class "Default")
      (node (ref "IC1") (pin "P$21") (pinfunction "SPK_P_P$21") (pintype "bidirectional"))
    )
    (net (code "106") (name "unconnected-(IC1-VDD_EXT-PadP$15)") (class "Default")
      (node (ref "IC1") (pin "P$15") (pinfunction "VDD_EXT_P$15") (pintype "bidirectional"))
    )
    (net (code "107") (name "unconnected-(J1-VPP-PadC6)") (class "Default")
      (node (ref "J1") (pin "C6") (pinfunction "VPP_C6") (pintype "input"))
    )
    (net (code "108") (name "unconnected-(K1-Pad1)") (class "Default")
      (node (ref "K1") (pin "1") (pinfunction "1_1") (pintype "passive"))
    )
    (net (code "109") (name "unconnected-(K1-Pad7)") (class "Default")
      (node (ref "K1") (pin "7") (pinfunction "7_7") (pintype "passive"))
    )
    (net (code "110") (name "unconnected-(K1-Pad12)") (class "Default")
      (node (ref "K1") (pin "12") (pinfunction "12_12") (pintype "passive"))
    )
    (net (code "111") (name "unconnected-(K1-Pad13)") (class "Default")
      (node (ref "K1") (pin "13") (pinfunction "13_13") (pintype "passive"))
    )
    (net (code "112") (name "unconnected-(K1-Pad16)") (class "Default")
      (node (ref "K1") (pin "16") (pinfunction "16_16") (pintype "passive"))
    )
    (net (code "113") (name "unconnected-(K1-Pad17)") (class "Default")
      (node (ref "K1") (pin "17") (pinfunction "17_17") (pintype "passive"))
    )
    (net (code "114") (name "unconnected-(K1-Pad18)") (class "Default")
      (node (ref "K1") (pin "18") (pinfunction "18_18") (pintype "passive"))
    )
    (net (code "115") (name "unconnected-(K1-Pad19)") (class "Default")
      (node (ref "K1") (pin "19") (pinfunction "19_19") (pintype "passive"))
    )
    (net (code "116") (name "unconnected-(K1-Pad21)") (class "Default")
      (node (ref "K1") (pin "21") (pinfunction "21_21") (pintype "passive"))
    )
    (net (code "117") (name "unconnected-(K1-Pad22)") (class "Default")
      (node (ref "K1") (pin "22") (pinfunction "22_22") (pintype "passive"))
    )
    (net (code "118") (name "unconnected-(K1-Pad23)") (class "Default")
      (node (ref "K1") (pin "23") (pinfunction "23_23") (pintype "passive"))
    )
    (net (code "119") (name "unconnected-(K1-Pad24)") (class "Default")
      (node (ref "K1") (pin "24") (pinfunction "24_24") (pintype "passive"))
    )
    (net (code "120") (name "unconnected-(K1-Pad26)") (class "Default")
      (node (ref "K1") (pin "26") (pinfunction "26_26") (pintype "passive"))
    )
    (net (code "121") (name "unconnected-(K1-Pad27)") (class "Default")
      (node (ref "K1") (pin "27") (pinfunction "27_27") (pintype "passive"))
    )
    (net (code "122") (name "unconnected-(K1-Pad28)") (class "Default")
      (node (ref "K1") (pin "28") (pinfunction "28_28") (pintype "passive"))
    )
    (net (code "123") (name "unconnected-(K1-Pad29)") (class "Default")
      (node (ref "K1") (pin "29") (pinfunction "29_29") (pintype "passive"))
    )
    (net (code "124") (name "unconnected-(K1-Pad31)") (class "Default")
      (node (ref "K1") (pin "31") (pinfunction "31_31") (pintype "passive"))
    )
    (net (code "125") (name "unconnected-(K1-Pad32)") (class "Default")
      (node (ref "K1") (pin "32") (pinfunction "32_32") (pintype "passive"))
    )
    (net (code "126") (name "unconnected-(K1-Pad33)") (class "Default")
      (node (ref "K1") (pin "33") (pinfunction "33_33") (pintype "passive"))
    )
    (net (code "127") (name "unconnected-(K1-Pad36)") (class "Default")
      (node (ref "K1") (pin "36") (pinfunction "36_36") (pintype "passive"))
    )
    (net (code "128") (name "unconnected-(K1-Pad38)") (class "Default")
      (node (ref "K1") (pin "38") (pinfunction "38_38") (pintype "passive"))
    )
    (net (code "129") (name "unconnected-(K1-Pad40)") (class "Default")
      (node (ref "K1") (pin "40") (pinfunction "40_40") (pintype "passive"))
    )
    (net (code "130") (name "unconnected-(U$1-*3-Pad6)") (class "Default")
      (node (ref "U$1") (pin "6") (pinfunction "*3_6") (pintype "bidirectional"))
    )
    (net (code "131") (name "unconnected-(U$1-*5-Pad8)") (class "Default")
      (node (ref "U$1") (pin "8") (pinfunction "*5_8") (pintype "bidirectional"))
    )
    (net (code "132") (name "unconnected-(U$1-*9-Pad12)") (class "Default")
      (node (ref "U$1") (pin "12") (pinfunction "*9_12") (pintype "bidirectional"))
    )
    (net (code "133") (name "unconnected-(U$1-*11-Pad14)") (class "Default")
      (node (ref "U$1") (pin "14") (pinfunction "*11_14") (pintype "bidirectional"))
    )
    (net (code "134") (name "unconnected-(U$1-2-Pad5)") (class "Default")
      (node (ref "U$1") (pin "5") (pinfunction "2_5") (pintype "bidirectional"))
    )
    (net (code "135") (name "unconnected-(U$1-4-Pad7)") (class "Default")
      (node (ref "U$1") (pin "7") (pinfunction "4_7") (pintype "bidirectional"))
    )
    (net (code "136") (name "unconnected-(U$1-7-Pad10)") (class "Default")
      (node (ref "U$1") (pin "10") (pinfunction "7_10") (pintype "bidirectional"))
    )
    (net (code "137") (name "unconnected-(U$1-8-Pad11)") (class "Default")
      (node (ref "U$1") (pin "11") (pinfunction "8_11") (pintype "bidirectional"))
    )
    (net (code "138") (name "unconnected-(U$1-12-Pad15)") (class "Default")
      (node (ref "U$1") (pin "15") (pinfunction "12_15") (pintype "bidirectional"))
    )
    (net (code "139") (name "unconnected-(U$1-13-Pad16)") (class "Default")
      (node (ref "U$1") (pin "16") (pinfunction "13_16") (pintype "bidirectional"))
    )
    (net (code "140") (name "unconnected-(U$1-RAW-Pad24)") (class "Default")
      (node (ref "U$1") (pin "24") (pinfunction "RAW_24") (pintype "bidirectional"))
    )
    (net (code "141") (name "unconnected-(U$1-RST-Pad3)") (class "Default")
      (node (ref "U$1") (pin "3") (pinfunction "RST_3") (pintype "bidirectional"))
    )
    (net (code "142") (name "unconnected-(U$1-RST-Pad22)") (class "Default")
      (node (ref "U$1") (pin "22") (pinfunction "RST_22") (pintype "bidirectional"))
    )
    (net (code "143") (name "unconnected-(U$3-IN-Pad3)") (class "Default")
      (node (ref "U$3") (pin "3") (pinfunction "IN_3") (pintype "bidirectional"))
    )
    (net (code "144") (name "unconnected-(U$8-2Y0-Pad2)") (class "Default")
      (node (ref "U$8") (pin "2") (pinfunction "2Y0_2") (pintype "bidirectional"))
    )
    (net (code "145") (name "unconnected-(U$8-2Y1-Pad1)") (class "Default")
      (node (ref "U$8") (pin "1") (pinfunction "2Y1_1") (pintype "bidirectional"))
    )
    (net (code "146") (name "unconnected-(U$8-2Z-Pad15)") (class "Default")
      (node (ref "U$8") (pin "15") (pinfunction "2Z_15") (pintype "bidirectional"))
    )
    (net (code "147") (name "unconnected-(U$8-3Y0-Pad5)") (class "Default")
      (node (ref "U$8") (pin "5") (pinfunction "3Y0_5") (pintype "bidirectional"))
    )
    (net (code "148") (name "unconnected-(U$8-3Y1-Pad3)") (class "Default")
      (node (ref "U$8") (pin "3") (pinfunction "3Y1_3") (pintype "bidirectional"))
    )
    (net (code "149") (name "unconnected-(U$8-3Z-Pad4)") (class "Default")
      (node (ref "U$8") (pin "4") (pinfunction "3Z_4") (pintype "bidirectional"))
    )
    (net (code "150") (name "unconnected-(U$8-S2-Pad10)") (class "Default")
      (node (ref "U$8") (pin "10") (pinfunction "S2_10") (pintype "bidirectional"))
    )
    (net (code "151") (name "unconnected-(U$8-S3-Pad9)") (class "Default")
      (node (ref "U$8") (pin "9") (pinfunction "S3_9") (pintype "bidirectional"))
    )
    (net (code "152") (name "unconnected-(U1-SQW{slash}OUT-Pad7)") (class "Default")
      (node (ref "U1") (pin "7") (pinfunction "SQW/OUT_7") (pintype "bidirectional"))
    )
    (net (code "153") (name "unconnected-(U3-PadNULL)") (class "Default")
      (node (ref "U3") (pin "NULL") (pinfunction "NULL_NULL") (pintype "no_connect"))
    )
  )
)
